# gps-tracker.net
KiCad netlist of a schematic drawn in EAGLE
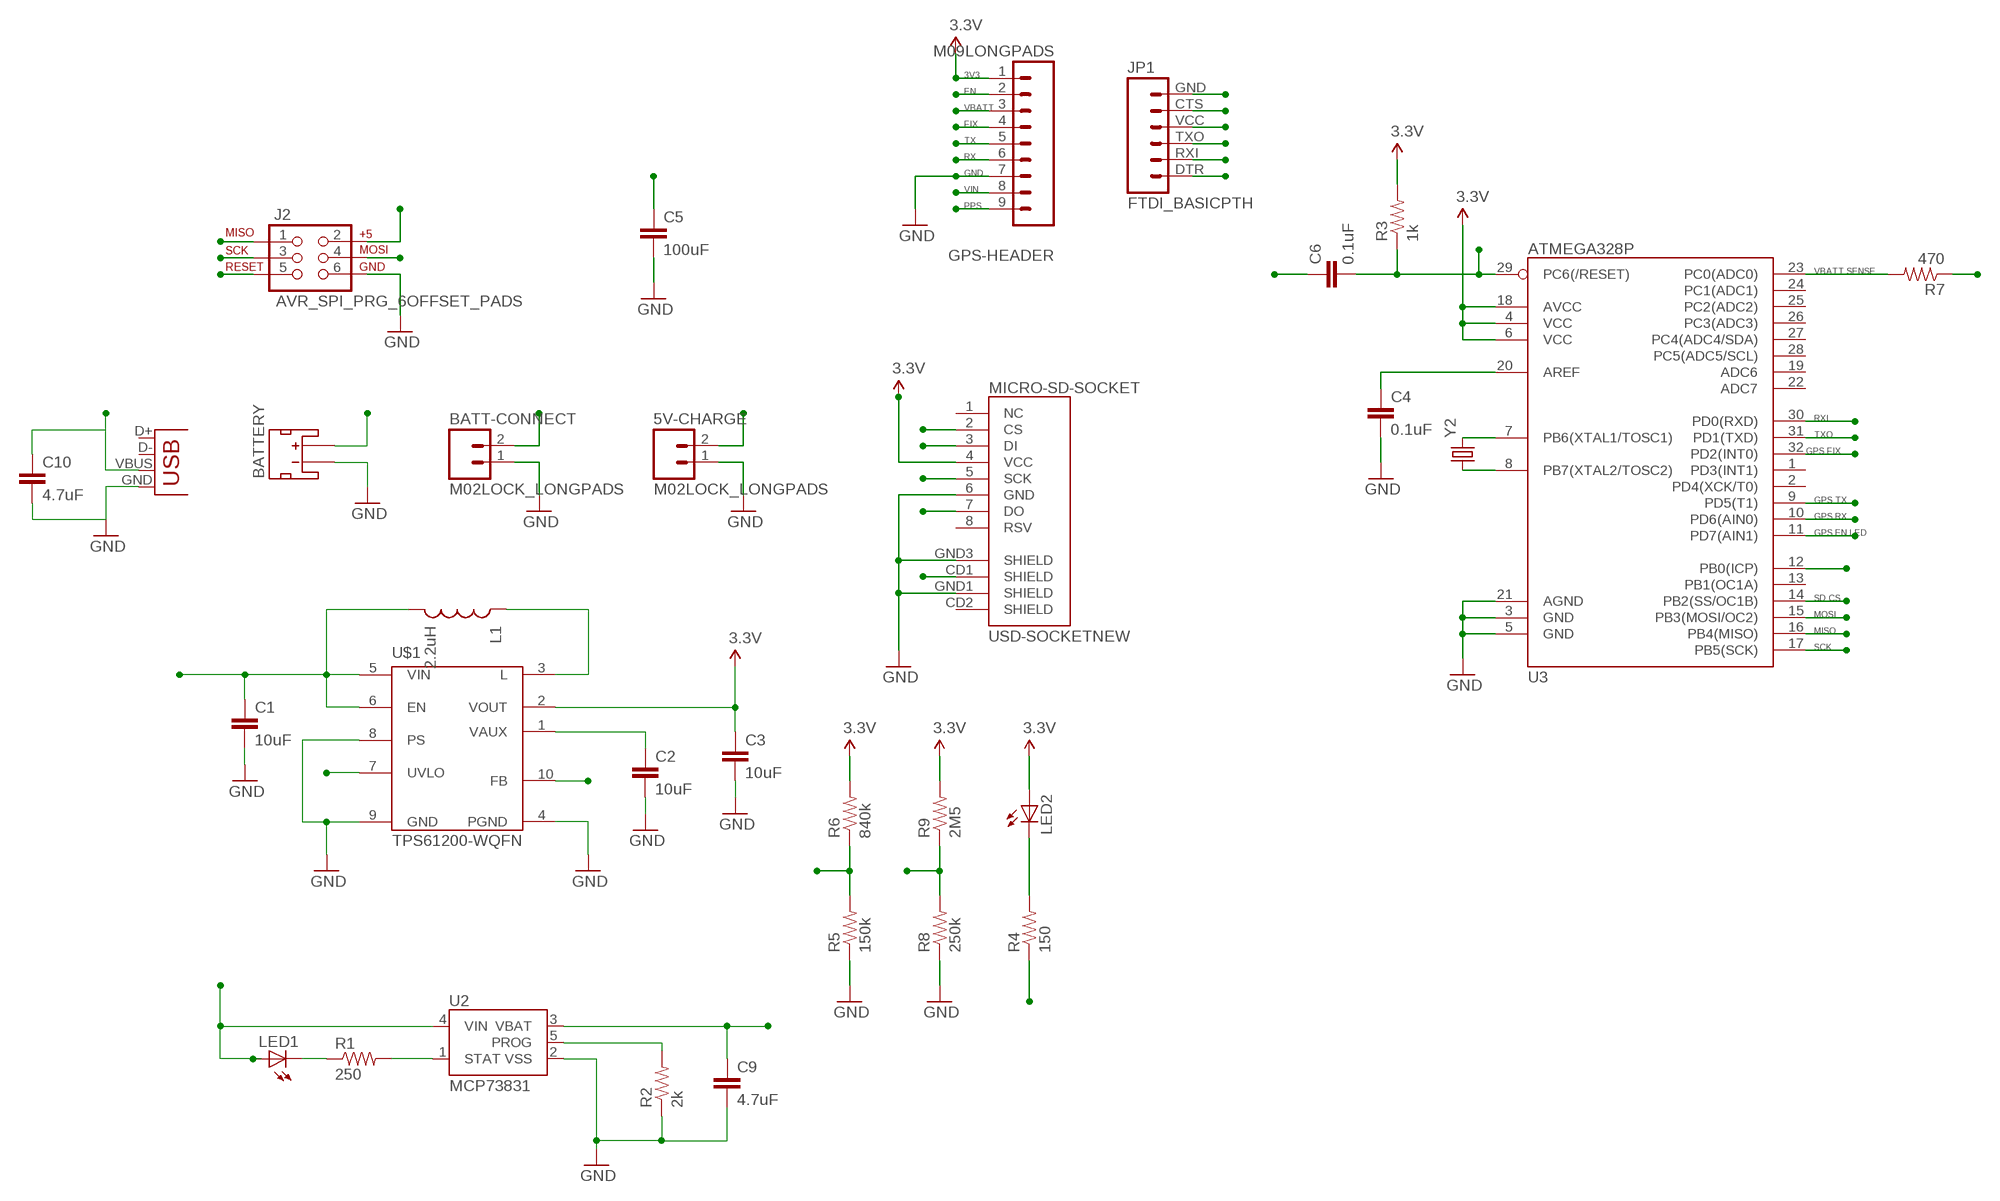
[diagram p0: schematic, sheet 1]

(export (version "E")
  (design (tool "Eeschema 10.0.6"))
  (components
    (comp (ref "5V-CHARGE")
      (value "M02LOCK_LONGPADS")
      (footprint "eagle-import:1X02_LOCK_LONGPADS")
      (libsource (lib "eagle-import") (part "M02LOCK_LONGPADS"))
    )
    (comp (ref "BATT-CONNECT")
      (value "M02LOCK_LONGPADS")
      (footprint "eagle-import:1X02_LOCK_LONGPADS")
      (libsource (lib "eagle-import") (part "M02LOCK_LONGPADS"))
    )
    (comp (ref "BATTERY")
      (value "JST_2MM_MALE")
      (footprint "eagle-import:JST-2-SMD")
      (libsource (lib "eagle-import") (part "JST_2MM_MALE"))
    )
    (comp (ref "C1")
      (value "10uF")
      (footprint "eagle-import:1206")
      (libsource (lib "eagle-import") (part "CAP1206"))
    )
    (comp (ref "C2")
      (value "10uF")
      (footprint "eagle-import:1206")
      (libsource (lib "eagle-import") (part "CAP1206"))
    )
    (comp (ref "C3")
      (value "10uF")
      (footprint "eagle-import:1206")
      (libsource (lib "eagle-import") (part "CAP1206"))
    )
    (comp (ref "C4")
      (value "0.1uF")
      (footprint "eagle-import:0603-CAP")
      (libsource (lib "eagle-import") (part "SparkFun-Capacitors_CAP0603-CAP"))
    )
    (comp (ref "C5")
      (value "100uF")
      (footprint "eagle-import:1206")
      (libsource (lib "eagle-import") (part "SparkFun-Capacitors_CAP1206"))
    )
    (comp (ref "C6")
      (value "0.1uF")
      (footprint "eagle-import:0603-CAP")
      (libsource (lib "eagle-import") (part "SparkFun-Capacitors_CAP0603-CAP"))
    )
    (comp (ref "C9")
      (value "4.7uF")
      (footprint "eagle-import:1206")
      (libsource (lib "eagle-import") (part "CAP1206"))
    )
    (comp (ref "C10")
      (value "4.7uF")
      (footprint "eagle-import:1206")
      (libsource (lib "eagle-import") (part "CAP1206"))
    )
    (comp (ref "GPS-HEADER")
      (value "M09LONGPADS")
      (footprint "eagle-import:1X09_LONGPADS")
      (libsource (lib "eagle-import") (part "M09LONGPADS"))
    )
    (comp (ref "J2")
      (value "AVR_SPI_PRG_6OFFSET_PADS")
      (footprint "eagle-import:2X3_OFFSET")
      (libsource (lib "eagle-import") (part "AVR_SPI_PRG_6OFFSET_PADS"))
    )
    (comp (ref "JP1")
      (value "FTDI_BASICPTH")
      (footprint "eagle-import:FTDI_BASIC")
      (libsource (lib "eagle-import") (part "FTDI_BASICPTH"))
    )
    (comp (ref "L1")
      (value "2.2uH")
      (footprint "eagle-import:CDRH3D28")
      (libsource (lib "eagle-import") (part "INDUCTOR-"))
    )
    (comp (ref "LED1")
      (value "LED0603")
      (footprint "eagle-import:LED-0603")
      (libsource (lib "eagle-import") (part "LED0603"))
    )
    (comp (ref "LED2")
      (value "LED5MM")
      (footprint "eagle-import:LED5MM")
      (libsource (lib "eagle-import") (part "SparkFun-LED_LED5MM"))
    )
    (comp (ref "MICRO-SD-SOCKET")
      (value "USD-SOCKETNEW")
      (footprint "eagle-import:MICRO-SD-SOCKET-PP")
      (libsource (lib "eagle-import") (part "USD-SOCKETNEW"))
    )
    (comp (ref "R1")
      (value "250")
      (footprint "eagle-import:0603-RES")
      (libsource (lib "eagle-import") (part "RESISTOR0603-RES"))
    )
    (comp (ref "R2")
      (value "2k")
      (footprint "eagle-import:0603-RES")
      (libsource (lib "eagle-import") (part "RESISTOR0603-RES"))
    )
    (comp (ref "R3")
      (value "1k")
      (footprint "eagle-import:0805")
      (libsource (lib "eagle-import") (part "RESISTOR0805-RES"))
    )
    (comp (ref "R4")
      (value "150")
      (footprint "eagle-import:0805")
      (libsource (lib "eagle-import") (part "RESISTOR0805-RES"))
    )
    (comp (ref "R5")
      (value "150k")
      (footprint "eagle-import:0603-RES")
      (libsource (lib "eagle-import") (part "RESISTOR0603-RES"))
    )
    (comp (ref "R6")
      (value "840k")
      (footprint "eagle-import:0603-RES")
      (libsource (lib "eagle-import") (part "RESISTOR0603-RES"))
    )
    (comp (ref "R7")
      (value "470")
      (footprint "eagle-import:0805")
      (libsource (lib "eagle-import") (part "RESISTOR0805-RES"))
    )
    (comp (ref "R8")
      (value "250k")
      (footprint "eagle-import:0603-RES")
      (libsource (lib "eagle-import") (part "RESISTOR0603-RES"))
    )
    (comp (ref "R9")
      (value "2M5")
      (footprint "eagle-import:0603-RES")
      (libsource (lib "eagle-import") (part "RESISTOR0603-RES"))
    )
    (comp (ref "U$1")
      (value "TPS61200-WQFN")
      (footprint "eagle-import:QFN-10")
      (libsource (lib "eagle-import") (part "TPS61200-WQFN"))
    )
    (comp (ref "U2")
      (value "MCP73831")
      (footprint "eagle-import:SOT23-5")
      (libsource (lib "eagle-import") (part "MCP73831"))
    )
    (comp (ref "U3")
      (value "ATMEGA328P")
      (footprint "eagle-import:TQFP32-08")
      (libsource (lib "eagle-import") (part "ATMEGA328_SMT"))
    )
    (comp (ref "X1")
      (value "USBSMD")
      (footprint "eagle-import:USB-MINIB")
      (libsource (lib "eagle-import") (part "USBSMD"))
    )
    (comp (ref "Y2")
      (value "CRYSTAL5X3")
      (footprint "eagle-import:CRYSTAL-SMD-5X3")
      (libsource (lib "eagle-import") (part "CRYSTAL5X3"))
    )
  )
  (nets
    (net (code "1") (name "/BATT_LED") (class "Default")
      (node (ref "R4") (pin "1") (pinfunction "1_1") (pintype "passive"))
      (node (ref "U3") (pin "12") (pinfunction "PB0(ICP)_12") (pintype "bidirectional"))
    )
    (net (code "2") (name "/DTR") (class "Default")
      (node (ref "C6") (pin "1") (pinfunction "1_1") (pintype "passive"))
      (node (ref "JP1") (pin "DTR") (pinfunction "1_DTR") (pintype "passive"))
    )
    (net (code "3") (name "/FB") (class "Default")
      (node (ref "R5") (pin "2") (pinfunction "2_2") (pintype "passive"))
      (node (ref "R6") (pin "1") (pinfunction "1_1") (pintype "passive"))
      (node (ref "U$1") (pin "10") (pinfunction "FB_10") (pintype "bidirectional"))
    )
    (net (code "4") (name "/GPS_FIX") (class "Default")
      (node (ref "GPS-HEADER") (pin "4") (pinfunction "4_4") (pintype "passive"))
      (node (ref "U3") (pin "32") (pinfunction "PD2(INT0)_32") (pintype "bidirectional"))
    )
    (net (code "5") (name "/GPS_RX") (class "Default")
      (node (ref "GPS-HEADER") (pin "6") (pinfunction "6_6") (pintype "passive"))
      (node (ref "U3") (pin "9") (pinfunction "PD5(T1)_9") (pintype "bidirectional"))
    )
    (net (code "6") (name "/GPS_TX") (class "Default")
      (node (ref "GPS-HEADER") (pin "5") (pinfunction "5_5") (pintype "passive"))
      (node (ref "U3") (pin "10") (pinfunction "PD6(AIN0)_10") (pintype "bidirectional"))
    )
    (net (code "7") (name "/MISO") (class "Default")
      (node (ref "J2") (pin "1") (pinfunction "1_1") (pintype "passive"))
      (node (ref "MICRO-SD-SOCKET") (pin "7") (pinfunction "DO_7") (pintype "bidirectional"))
      (node (ref "U3") (pin "16") (pinfunction "PB4(MISO)_16") (pintype "bidirectional"))
    )
    (net (code "8") (name "/MOSI") (class "Default")
      (node (ref "J2") (pin "4") (pinfunction "4_4") (pintype "passive"))
      (node (ref "MICRO-SD-SOCKET") (pin "3") (pinfunction "DI_3") (pintype "bidirectional"))
      (node (ref "U3") (pin "15") (pinfunction "PB3(MOSI/OC2)_15") (pintype "bidirectional"))
    )
    (net (code "9") (name "/RXI") (class "Default")
      (node (ref "JP1") (pin "TXO") (pinfunction "3_TXO") (pintype "passive"))
      (node (ref "U3") (pin "31") (pinfunction "PD1(TXD)_31") (pintype "bidirectional"))
    )
    (net (code "10") (name "/SCK") (class "Default")
      (node (ref "J2") (pin "3") (pinfunction "3_3") (pintype "passive"))
      (node (ref "MICRO-SD-SOCKET") (pin "5") (pinfunction "SCK_5") (pintype "bidirectional"))
      (node (ref "U3") (pin "17") (pinfunction "PB5(SCK)_17") (pintype "bidirectional"))
    )
    (net (code "11") (name "/SD_CS") (class "Default")
      (node (ref "MICRO-SD-SOCKET") (pin "2") (pinfunction "CS_2") (pintype "bidirectional"))
      (node (ref "U3") (pin "14") (pinfunction "PB2(SS/OC1B)_14") (pintype "bidirectional"))
    )
    (net (code "12") (name "/TXO") (class "Default")
      (node (ref "JP1") (pin "RXI") (pinfunction "2_RXI") (pintype "passive"))
      (node (ref "U3") (pin "30") (pinfunction "PD0(RXD)_30") (pintype "bidirectional"))
    )
    (net (code "13") (name "/UVLO") (class "Default")
      (node (ref "R8") (pin "2") (pinfunction "2_2") (pintype "passive"))
      (node (ref "R9") (pin "1") (pinfunction "1_1") (pintype "passive"))
      (node (ref "U$1") (pin "7") (pinfunction "UVLO_7") (pintype "bidirectional"))
    )
    (net (code "14") (name "/VBATT") (class "Default")
      (node (ref "BATT-CONNECT") (pin "2") (pinfunction "2_2") (pintype "passive"))
      (node (ref "BATTERY") (pin "2") (pinfunction "+_2") (pintype "bidirectional"))
      (node (ref "C1") (pin "1") (pinfunction "1_1") (pintype "passive"))
      (node (ref "C5") (pin "1") (pinfunction "1_1") (pintype "passive"))
      (node (ref "C9") (pin "1") (pinfunction "1_1") (pintype "passive"))
      (node (ref "L1") (pin "2") (pinfunction "2_2") (pintype "passive"))
      (node (ref "R7") (pin "1") (pinfunction "1_1") (pintype "passive"))
      (node (ref "U$1") (pin "5") (pinfunction "VIN_5") (pintype "bidirectional"))
      (node (ref "U$1") (pin "6") (pinfunction "EN_6") (pintype "bidirectional"))
      (node (ref "U2") (pin "3") (pinfunction "VBAT_3") (pintype "power_in"))
    )
    (net (code "15") (name "/VUSB") (class "Default")
      (node (ref "5V-CHARGE") (pin "2") (pinfunction "2_2") (pintype "passive"))
      (node (ref "C10") (pin "1") (pinfunction "1_1") (pintype "passive"))
      (node (ref "LED1") (pin "A") (pinfunction "A_A") (pintype "passive"))
      (node (ref "U2") (pin "4") (pinfunction "VIN_4") (pintype "power_in"))
      (node (ref "X1") (pin "VBUS") (pinfunction "VBUS_VBUS") (pintype "bidirectional"))
    )
    (net (code "16") (name "/{slash}RESET") (class "Default")
      (node (ref "C6") (pin "2") (pinfunction "2_2") (pintype "passive"))
      (node (ref "J2") (pin "5") (pinfunction "5_5") (pintype "passive"))
      (node (ref "R3") (pin "1") (pinfunction "1_1") (pintype "passive"))
      (node (ref "U3") (pin "29") (pinfunction "PC6(/RESET)_29") (pintype "bidirectional"))
    )
    (net (code "17") (name "3.3V") (class "Default")
      (node (ref "C3") (pin "1") (pinfunction "1_1") (pintype "passive"))
      (node (ref "GPS-HEADER") (pin "1") (pinfunction "1_1") (pintype "passive"))
      (node (ref "LED2") (pin "A") (pinfunction "A_A") (pintype "passive"))
      (node (ref "MICRO-SD-SOCKET") (pin "4") (pinfunction "VCC_4") (pintype "bidirectional"))
      (node (ref "R3") (pin "2") (pinfunction "2_2") (pintype "passive"))
      (node (ref "R6") (pin "2") (pinfunction "2_2") (pintype "passive"))
      (node (ref "R9") (pin "2") (pinfunction "2_2") (pintype "passive"))
      (node (ref "U$1") (pin "2") (pinfunction "VOUT_2") (pintype "bidirectional"))
      (node (ref "U3") (pin "18") (pinfunction "AVCC_18") (pintype "bidirectional"))
      (node (ref "U3") (pin "4") (pinfunction "VCC_4") (pintype "bidirectional"))
      (node (ref "U3") (pin "6") (pinfunction "VCC_6") (pintype "bidirectional"))
    )
    (net (code "18") (name "GND") (class "Default")
      (node (ref "5V-CHARGE") (pin "1") (pinfunction "1_1") (pintype "passive"))
      (node (ref "BATT-CONNECT") (pin "1") (pinfunction "1_1") (pintype "passive"))
      (node (ref "BATTERY") (pin "1") (pinfunction "-_1") (pintype "bidirectional"))
      (node (ref "C1") (pin "2") (pinfunction "2_2") (pintype "passive"))
      (node (ref "C10") (pin "2") (pinfunction "2_2") (pintype "passive"))
      (node (ref "C2") (pin "2") (pinfunction "2_2") (pintype "passive"))
      (node (ref "C3") (pin "2") (pinfunction "2_2") (pintype "passive"))
      (node (ref "C4") (pin "2") (pinfunction "2_2") (pintype "passive"))
      (node (ref "C5") (pin "2") (pinfunction "2_2") (pintype "passive"))
      (node (ref "C9") (pin "2") (pinfunction "2_2") (pintype "passive"))
      (node (ref "GPS-HEADER") (pin "7") (pinfunction "7_7") (pintype "passive"))
      (node (ref "J2") (pin "6") (pinfunction "6_6") (pintype "passive"))
      (node (ref "JP1") (pin "CTS") (pinfunction "5_CTS") (pintype "passive"))
      (node (ref "JP1") (pin "GND") (pinfunction "6_GND") (pintype "passive"))
      (node (ref "MICRO-SD-SOCKET") (pin "6") (pinfunction "GND_6") (pintype "bidirectional"))
      (node (ref "MICRO-SD-SOCKET") (pin "GND1") (pinfunction "SHIELD_GND1") (pintype "bidirectional"))
      (node (ref "MICRO-SD-SOCKET") (pin "GND3") (pinfunction "SHIELD_GND3") (pintype "bidirectional"))
      (node (ref "R2") (pin "1") (pinfunction "1_1") (pintype "passive"))
      (node (ref "R5") (pin "1") (pinfunction "1_1") (pintype "passive"))
      (node (ref "R8") (pin "1") (pinfunction "1_1") (pintype "passive"))
      (node (ref "U$1") (pin "4") (pinfunction "PGND_4") (pintype "bidirectional"))
      (node (ref "U$1") (pin "8") (pinfunction "PS_8") (pintype "bidirectional"))
      (node (ref "U$1") (pin "9") (pinfunction "GND_9") (pintype "bidirectional"))
      (node (ref "U2") (pin "2") (pinfunction "VSS_2") (pintype "power_in"))
      (node (ref "U3") (pin "21") (pinfunction "AGND_21") (pintype "bidirectional"))
      (node (ref "U3") (pin "3") (pinfunction "GND_3") (pintype "bidirectional"))
      (node (ref "U3") (pin "5") (pinfunction "GND_5") (pintype "bidirectional"))
      (node (ref "X1") (pin "GND") (pinfunction "GND_GND") (pintype "bidirectional"))
    )
    (net (code "19") (name "Net-(LED1-PadC)") (class "Default")
      (node (ref "LED1") (pin "C") (pinfunction "C_C") (pintype "passive"))
      (node (ref "R1") (pin "1") (pinfunction "1_1") (pintype "passive"))
    )
    (net (code "20") (name "Net-(LED2-C)") (class "Default")
      (node (ref "LED2") (pin "K") (pinfunction "C_K") (pintype "passive"))
      (node (ref "R4") (pin "2") (pinfunction "2_2") (pintype "passive"))
    )
    (net (code "21") (name "Net-(U$1-L)") (class "Default")
      (node (ref "L1") (pin "1") (pinfunction "1_1") (pintype "passive"))
      (node (ref "U$1") (pin "3") (pinfunction "L_3") (pintype "bidirectional"))
    )
    (net (code "22") (name "Net-(U$1-VAUX)") (class "Default")
      (node (ref "C2") (pin "1") (pinfunction "1_1") (pintype "passive"))
      (node (ref "U$1") (pin "1") (pinfunction "VAUX_1") (pintype "bidirectional"))
    )
    (net (code "23") (name "Net-(U2-PROG)") (class "Default")
      (node (ref "R2") (pin "2") (pinfunction "2_2") (pintype "passive"))
      (node (ref "U2") (pin "5") (pinfunction "PROG_5") (pintype "input"))
    )
    (net (code "24") (name "Net-(U2-STAT)") (class "Default")
      (node (ref "R1") (pin "2") (pinfunction "2_2") (pintype "passive"))
      (node (ref "U2") (pin "1") (pinfunction "STAT_1") (pintype "output"))
    )
    (net (code "25") (name "Net-(U3-AREF)") (class "Default")
      (node (ref "C4") (pin "1") (pinfunction "1_1") (pintype "passive"))
      (node (ref "U3") (pin "20") (pinfunction "AREF_20") (pintype "bidirectional"))
    )
    (net (code "26") (name "Net-(U3-PB6(XTAL1{slash}TOSC1))") (class "Default")
      (node (ref "U3") (pin "7") (pinfunction "PB6(XTAL1/TOSC1)_7") (pintype "bidirectional"))
      (node (ref "Y2") (pin "3") (pinfunction "2_3") (pintype "passive"))
    )
    (net (code "27") (name "Net-(U3-PB7(XTAL2{slash}TOSC2))") (class "Default")
      (node (ref "U3") (pin "8") (pinfunction "PB7(XTAL2/TOSC2)_8") (pintype "bidirectional"))
      (node (ref "Y2") (pin "1") (pinfunction "1_1") (pintype "passive"))
    )
    (net (code "28") (name "Net-(U3-PC0(ADC0))") (class "Default")
      (node (ref "R7") (pin "2") (pinfunction "2_2") (pintype "passive"))
      (node (ref "U3") (pin "23") (pinfunction "PC0(ADC0)_23") (pintype "bidirectional"))
    )
    (net (code "29") (name "unconnected-(BATTERY-PAD1-PadNC1)") (class "Default")
      (node (ref "BATTERY") (pin "NC1") (pinfunction "PAD1_NC1") (pintype "bidirectional"))
    )
    (net (code "30") (name "unconnected-(BATTERY-PAD2-PadNC2)") (class "Default")
      (node (ref "BATTERY") (pin "NC2") (pinfunction "PAD2_NC2") (pintype "bidirectional"))
    )
    (net (code "31") (name "unconnected-(GPS-HEADER-Pad2)") (class "Default")
      (node (ref "GPS-HEADER") (pin "2") (pinfunction "2_2") (pintype "passive"))
    )
    (net (code "32") (name "unconnected-(GPS-HEADER-Pad3)") (class "Default")
      (node (ref "GPS-HEADER") (pin "3") (pinfunction "3_3") (pintype "passive"))
    )
    (net (code "33") (name "unconnected-(GPS-HEADER-Pad8)") (class "Default")
      (node (ref "GPS-HEADER") (pin "8") (pinfunction "8_8") (pintype "passive"))
    )
    (net (code "34") (name "unconnected-(GPS-HEADER-Pad9)") (class "Default")
      (node (ref "GPS-HEADER") (pin "9") (pinfunction "9_9") (pintype "passive"))
    )
    (net (code "35") (name "unconnected-(J2-Pad2)") (class "Default")
      (node (ref "J2") (pin "2") (pinfunction "2_2") (pintype "passive"))
    )
    (net (code "36") (name "unconnected-(JP1-4-PadVCC)") (class "Default")
      (node (ref "JP1") (pin "VCC") (pinfunction "4_VCC") (pintype "passive"))
    )
    (net (code "37") (name "unconnected-(MICRO-SD-SOCKET-NC-Pad1)") (class "Default")
      (node (ref "MICRO-SD-SOCKET") (pin "1") (pinfunction "NC_1") (pintype "bidirectional"))
    )
    (net (code "38") (name "unconnected-(MICRO-SD-SOCKET-RSV-Pad8)") (class "Default")
      (node (ref "MICRO-SD-SOCKET") (pin "8") (pinfunction "RSV_8") (pintype "bidirectional"))
    )
    (net (code "39") (name "unconnected-(MICRO-SD-SOCKET-SHIELD-PadCD1)") (class "Default")
      (node (ref "MICRO-SD-SOCKET") (pin "CD1") (pinfunction "SHIELD_CD1") (pintype "bidirectional"))
    )
    (net (code "40") (name "unconnected-(MICRO-SD-SOCKET-SHIELD-PadCD2)") (class "Default")
      (node (ref "MICRO-SD-SOCKET") (pin "CD2") (pinfunction "SHIELD_CD2") (pintype "bidirectional"))
    )
    (net (code "41") (name "unconnected-(U3-ADC6-Pad19)") (class "Default")
      (node (ref "U3") (pin "19") (pinfunction "ADC6_19") (pintype "bidirectional"))
    )
    (net (code "42") (name "unconnected-(U3-ADC7-Pad22)") (class "Default")
      (node (ref "U3") (pin "22") (pinfunction "ADC7_22") (pintype "bidirectional"))
    )
    (net (code "43") (name "unconnected-(U3-PB1(OC1A)-Pad13)") (class "Default")
      (node (ref "U3") (pin "13") (pinfunction "PB1(OC1A)_13") (pintype "bidirectional"))
    )
    (net (code "44") (name "unconnected-(U3-PC1(ADC1)-Pad24)") (class "Default")
      (node (ref "U3") (pin "24") (pinfunction "PC1(ADC1)_24") (pintype "bidirectional"))
    )
    (net (code "45") (name "unconnected-(U3-PC2(ADC2)-Pad25)") (class "Default")
      (node (ref "U3") (pin "25") (pinfunction "PC2(ADC2)_25") (pintype "bidirectional"))
    )
    (net (code "46") (name "unconnected-(U3-PC3(ADC3)-Pad26)") (class "Default")
      (node (ref "U3") (pin "26") (pinfunction "PC3(ADC3)_26") (pintype "bidirectional"))
    )
    (net (code "47") (name "unconnected-(U3-PC4(ADC4{slash}SDA)-Pad27)") (class "Default")
      (node (ref "U3") (pin "27") (pinfunction "PC4(ADC4/SDA)_27") (pintype "bidirectional"))
    )
    (net (code "48") (name "unconnected-(U3-PC5(ADC5{slash}SCL)-Pad28)") (class "Default")
      (node (ref "U3") (pin "28") (pinfunction "PC5(ADC5/SCL)_28") (pintype "bidirectional"))
    )
    (net (code "49") (name "unconnected-(U3-PD3(INT1)-Pad1)") (class "Default")
      (node (ref "U3") (pin "1") (pinfunction "PD3(INT1)_1") (pintype "bidirectional"))
    )
    (net (code "50") (name "unconnected-(U3-PD4(XCK{slash}T0)-Pad2)") (class "Default")
      (node (ref "U3") (pin "2") (pinfunction "PD4(XCK/T0)_2") (pintype "bidirectional"))
    )
    (net (code "51") (name "unconnected-(U3-PD7(AIN1)-Pad11)") (class "Default")
      (node (ref "U3") (pin "11") (pinfunction "PD7(AIN1)_11") (pintype "bidirectional"))
    )
    (net (code "52") (name "unconnected-(X1-PadD+)") (class "Default")
      (node (ref "X1") (pin "D+") (pinfunction "D+_D+") (pintype "bidirectional"))
    )
    (net (code "53") (name "unconnected-(X1-PadD-)") (class "Default")
      (node (ref "X1") (pin "D-") (pinfunction "D-_D-") (pintype "bidirectional"))
    )
  )
)
